# module_xbee-_Schema_electrique.net
KiCad netlist of a schematic drawn in EAGLE
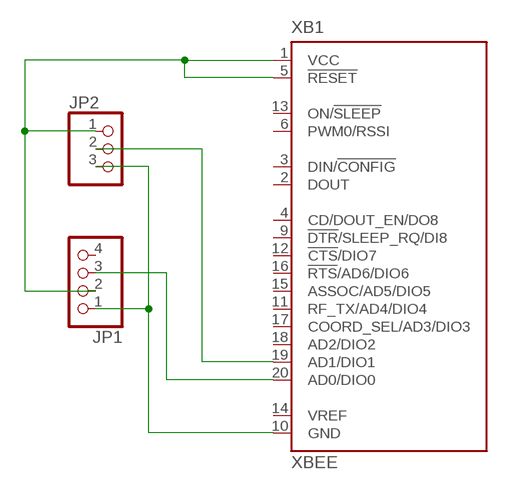
[diagram p0: schematic, sheet 1]

(export (version "E")
  (design (tool "Eeschema 10.0.6"))
  (components
    (comp (ref "JP1")
      (value "PINHD-1X4")
      (footprint "eagle-import:1X04")
      (libsource (lib "eagle-import") (part "PINHD-1X4"))
    )
    (comp (ref "JP2")
      (value "PINHD-1X3")
      (footprint "eagle-import:1X03")
      (libsource (lib "eagle-import") (part "PINHD-1X3"))
    )
    (comp (ref "XB1")
      (value "XBEE")
      (footprint "eagle-import:XBEE")
      (fields (field (name "MPN") "XBP24-Z7UIT-004"))
      (libsource (lib "eagle-import") (part "XBEE"))
    )
  )
  (nets
    (net (code "1") (name "Net-(XB1-AD0{slash}DIO0)") (class "Default")
      (node (ref "JP1") (pin "3") (pinfunction "3_3") (pintype "passive"))
      (node (ref "XB1") (pin "20") (pinfunction "AD0/DIO0_20") (pintype "bidirectional"))
    )
    (net (code "2") (name "Net-(XB1-AD1{slash}DIO1)") (class "Default")
      (node (ref "JP2") (pin "2") (pinfunction "2_2") (pintype "passive"))
      (node (ref "XB1") (pin "19") (pinfunction "AD1/DIO1_19") (pintype "bidirectional"))
    )
    (net (code "3") (name "Net-(XB1-GND)") (class "Default")
      (node (ref "JP1") (pin "1") (pinfunction "1_1") (pintype "passive"))
      (node (ref "JP2") (pin "3") (pinfunction "3_3") (pintype "passive"))
      (node (ref "XB1") (pin "10") (pinfunction "GND_10") (pintype "power_in"))
    )
    (net (code "4") (name "Net-(XB1-VCC)") (class "Default")
      (node (ref "JP1") (pin "2") (pinfunction "2_2") (pintype "passive"))
      (node (ref "JP2") (pin "1") (pinfunction "1_1") (pintype "passive"))
      (node (ref "XB1") (pin "1") (pinfunction "VCC_1") (pintype "power_in"))
      (node (ref "XB1") (pin "5") (pinfunction "~{RESET}_5") (pintype "input"))
    )
    (net (code "5") (name "unconnected-(JP1-Pad4)") (class "Default")
      (node (ref "JP1") (pin "4") (pinfunction "4_4") (pintype "passive"))
    )
    (net (code "6") (name "unconnected-(XB1-AD2{slash}DIO2-Pad18)") (class "Default")
      (node (ref "XB1") (pin "18") (pinfunction "AD2/DIO2_18") (pintype "bidirectional"))
    )
    (net (code "7") (name "unconnected-(XB1-ASSOC{slash}AD5{slash}DIO5-Pad15)") (class "Default")
      (node (ref "XB1") (pin "15") (pinfunction "ASSOC/AD5/DIO5_15") (pintype "bidirectional"))
    )
    (net (code "8") (name "unconnected-(XB1-CD{slash}DOUT_EN{slash}DO8-Pad4)") (class "Default")
      (node (ref "XB1") (pin "4") (pinfunction "CD/DOUT_EN/DO8_4") (pintype "output"))
    )
    (net (code "9") (name "unconnected-(XB1-COORD_SEL{slash}AD3{slash}DIO3-Pad17)") (class "Default")
      (node (ref "XB1") (pin "17") (pinfunction "COORD_SEL/AD3/DIO3_17") (pintype "bidirectional"))
    )
    (net (code "10") (name "unconnected-(XB1-DIN{slash}~{CONFIG}-Pad3)") (class "Default")
      (node (ref "XB1") (pin "3") (pinfunction "DIN/~{CONFIG}_3") (pintype "input"))
    )
    (net (code "11") (name "unconnected-(XB1-DOUT-Pad2)") (class "Default")
      (node (ref "XB1") (pin "2") (pinfunction "DOUT_2") (pintype "output"))
    )
    (net (code "12") (name "unconnected-(XB1-ON{slash}~{SLEEP}-Pad13)") (class "Default")
      (node (ref "XB1") (pin "13") (pinfunction "ON/~{SLEEP}_13") (pintype "output"))
    )
    (net (code "13") (name "unconnected-(XB1-PWM0{slash}RSSI-Pad6)") (class "Default")
      (node (ref "XB1") (pin "6") (pinfunction "PWM0/RSSI_6") (pintype "output"))
    )
    (net (code "14") (name "unconnected-(XB1-RF_TX{slash}AD4{slash}DIO4-Pad11)") (class "Default")
      (node (ref "XB1") (pin "11") (pinfunction "RF_TX/AD4/DIO4_11") (pintype "bidirectional"))
    )
    (net (code "15") (name "unconnected-(XB1-VREF-Pad14)") (class "Default")
      (node (ref "XB1") (pin "14") (pinfunction "VREF_14") (pintype "input"))
    )
    (net (code "16") (name "unconnected-(XB1-~{CTS}{slash}DIO7-Pad12)") (class "Default")
      (node (ref "XB1") (pin "12") (pinfunction "~{CTS}/DIO7_12") (pintype "bidirectional"))
    )
    (net (code "17") (name "unconnected-(XB1-~{DTR}{slash}SLEEP_RQ{slash}DI8-Pad9)") (class "Default")
      (node (ref "XB1") (pin "9") (pinfunction "~{DTR}/SLEEP_RQ/DI8_9") (pintype "bidirectional"))
    )
    (net (code "18") (name "unconnected-(XB1-~{RTS}{slash}AD6{slash}DIO6-Pad16)") (class "Default")
      (node (ref "XB1") (pin "16") (pinfunction "~{RTS}/AD6/DIO6_16") (pintype "bidirectional"))
    )
  )
)
